# ble-jig-v1_0.net
KiCad netlist of a schematic drawn in EAGLE
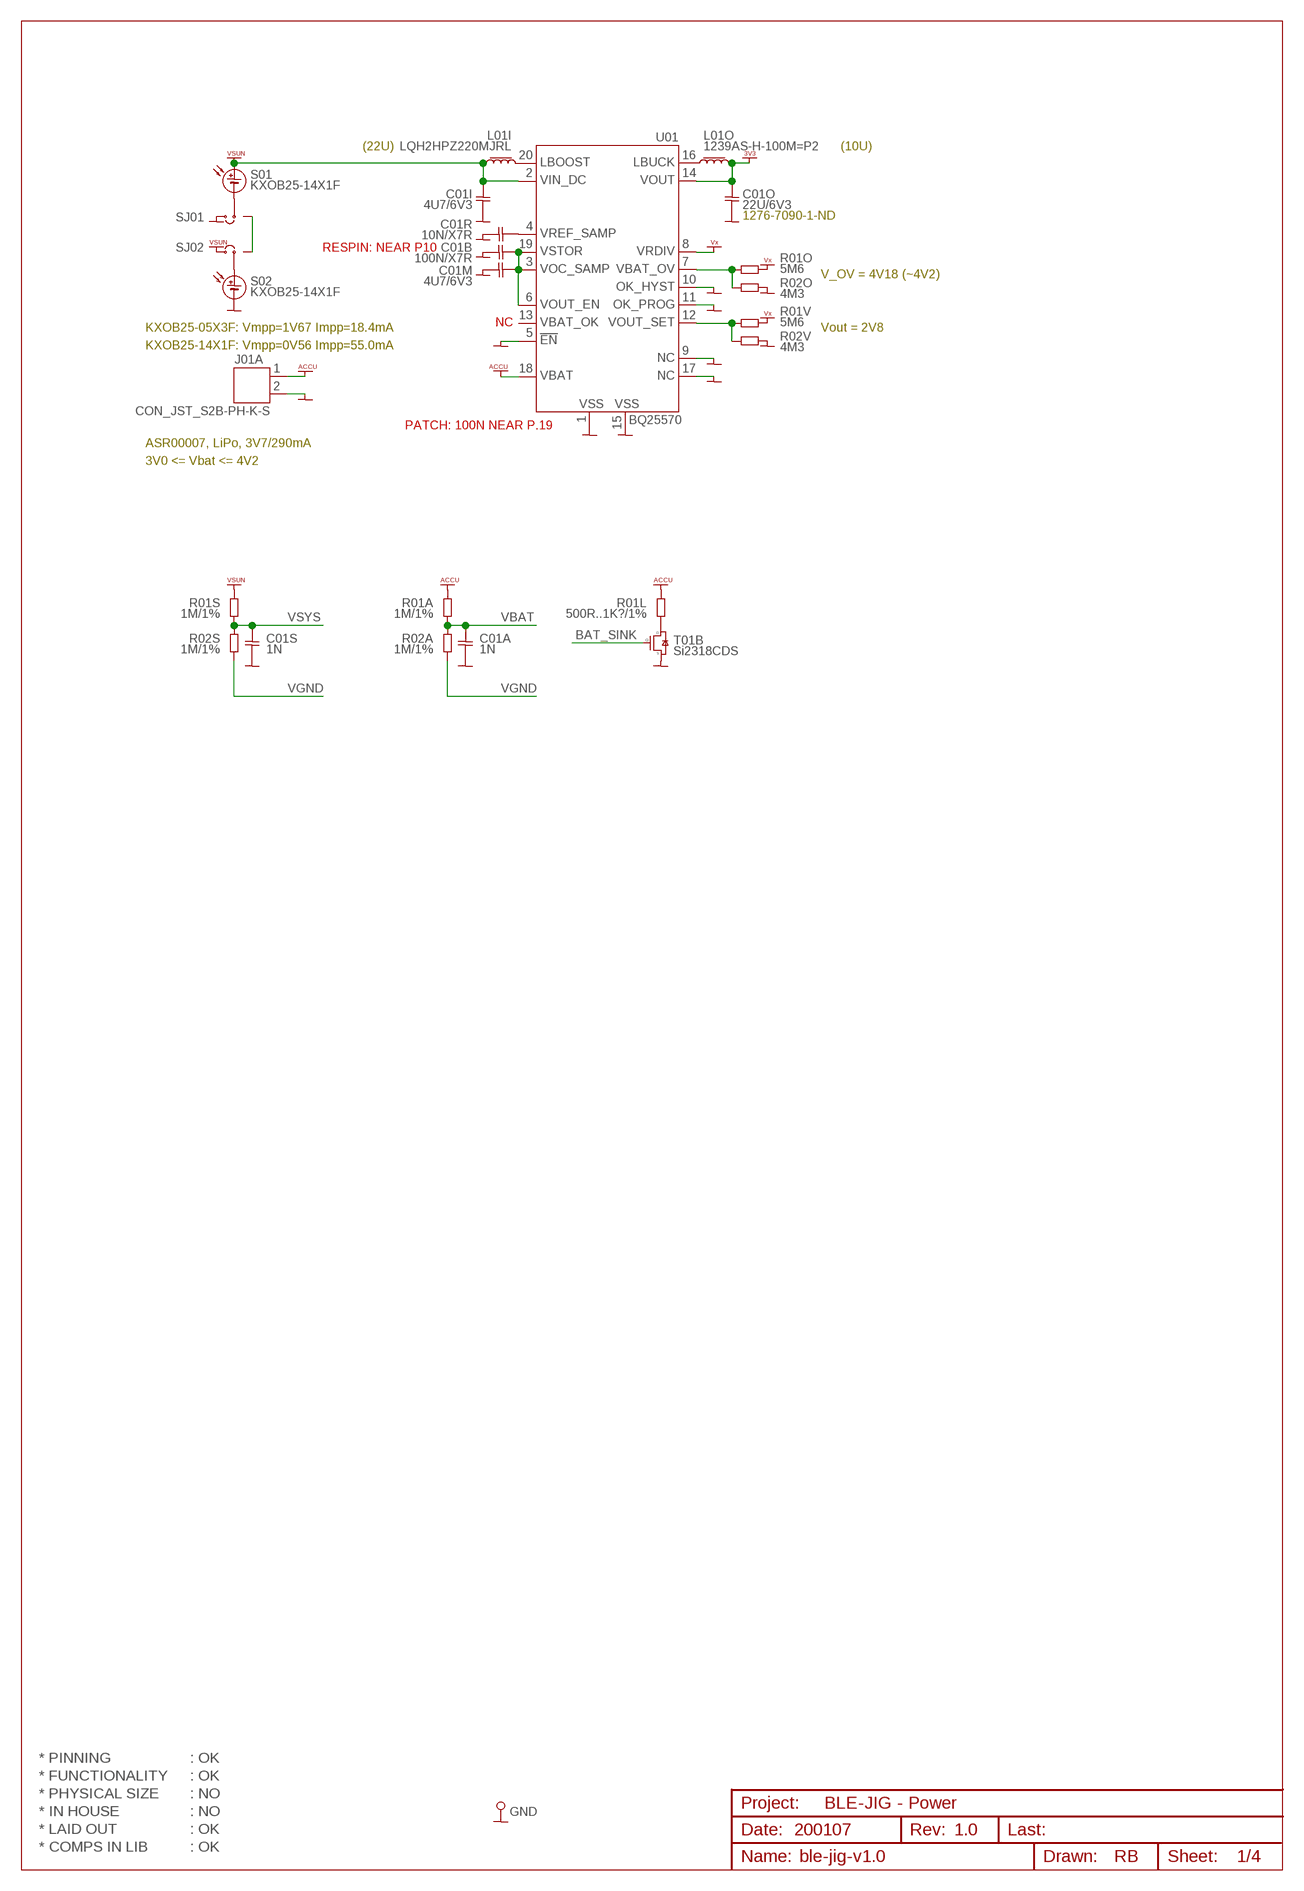
[diagram p0: schematic, sheet 1]
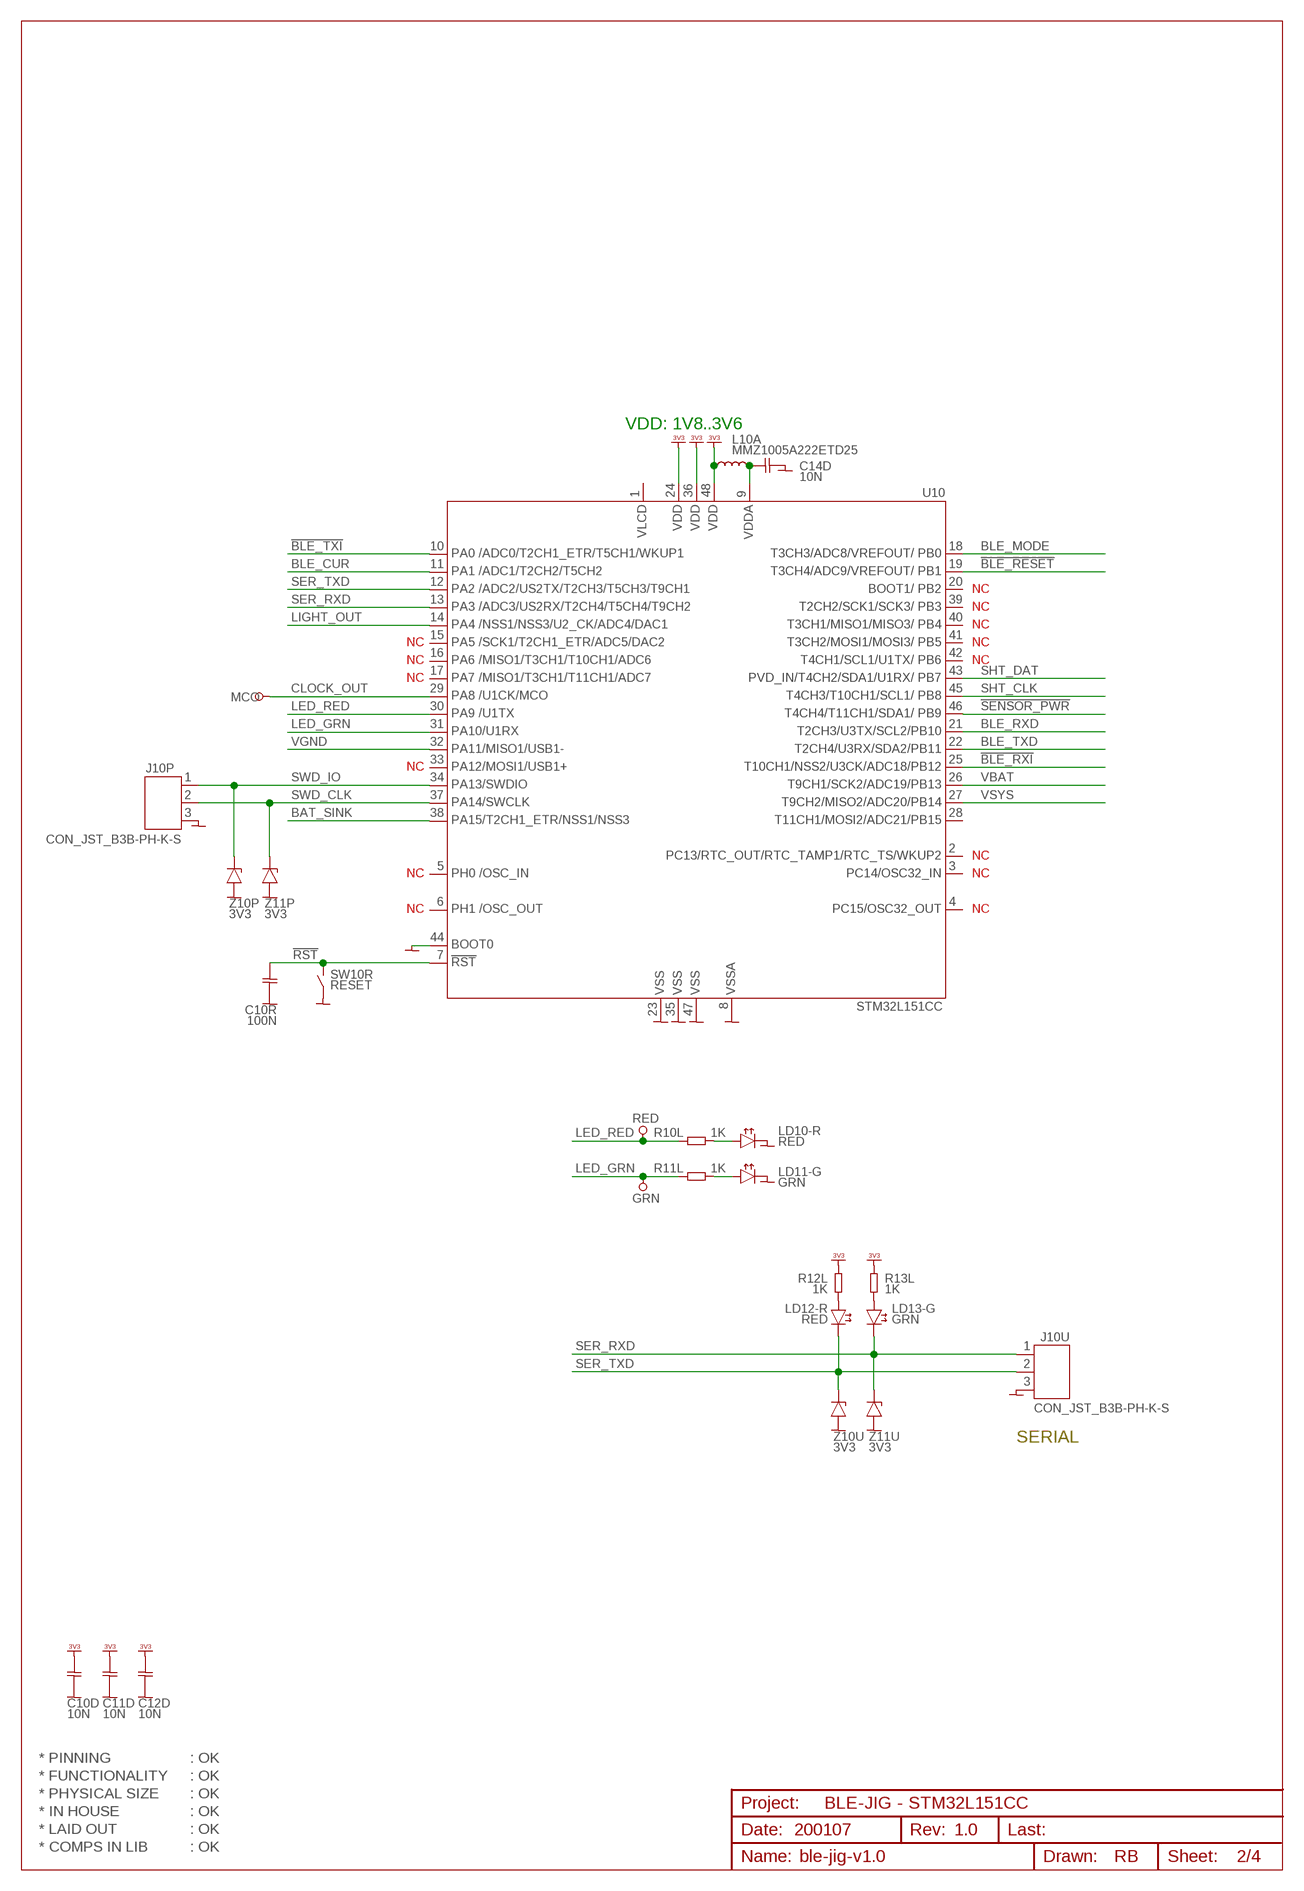
[diagram p1: schematic, sheet 2]
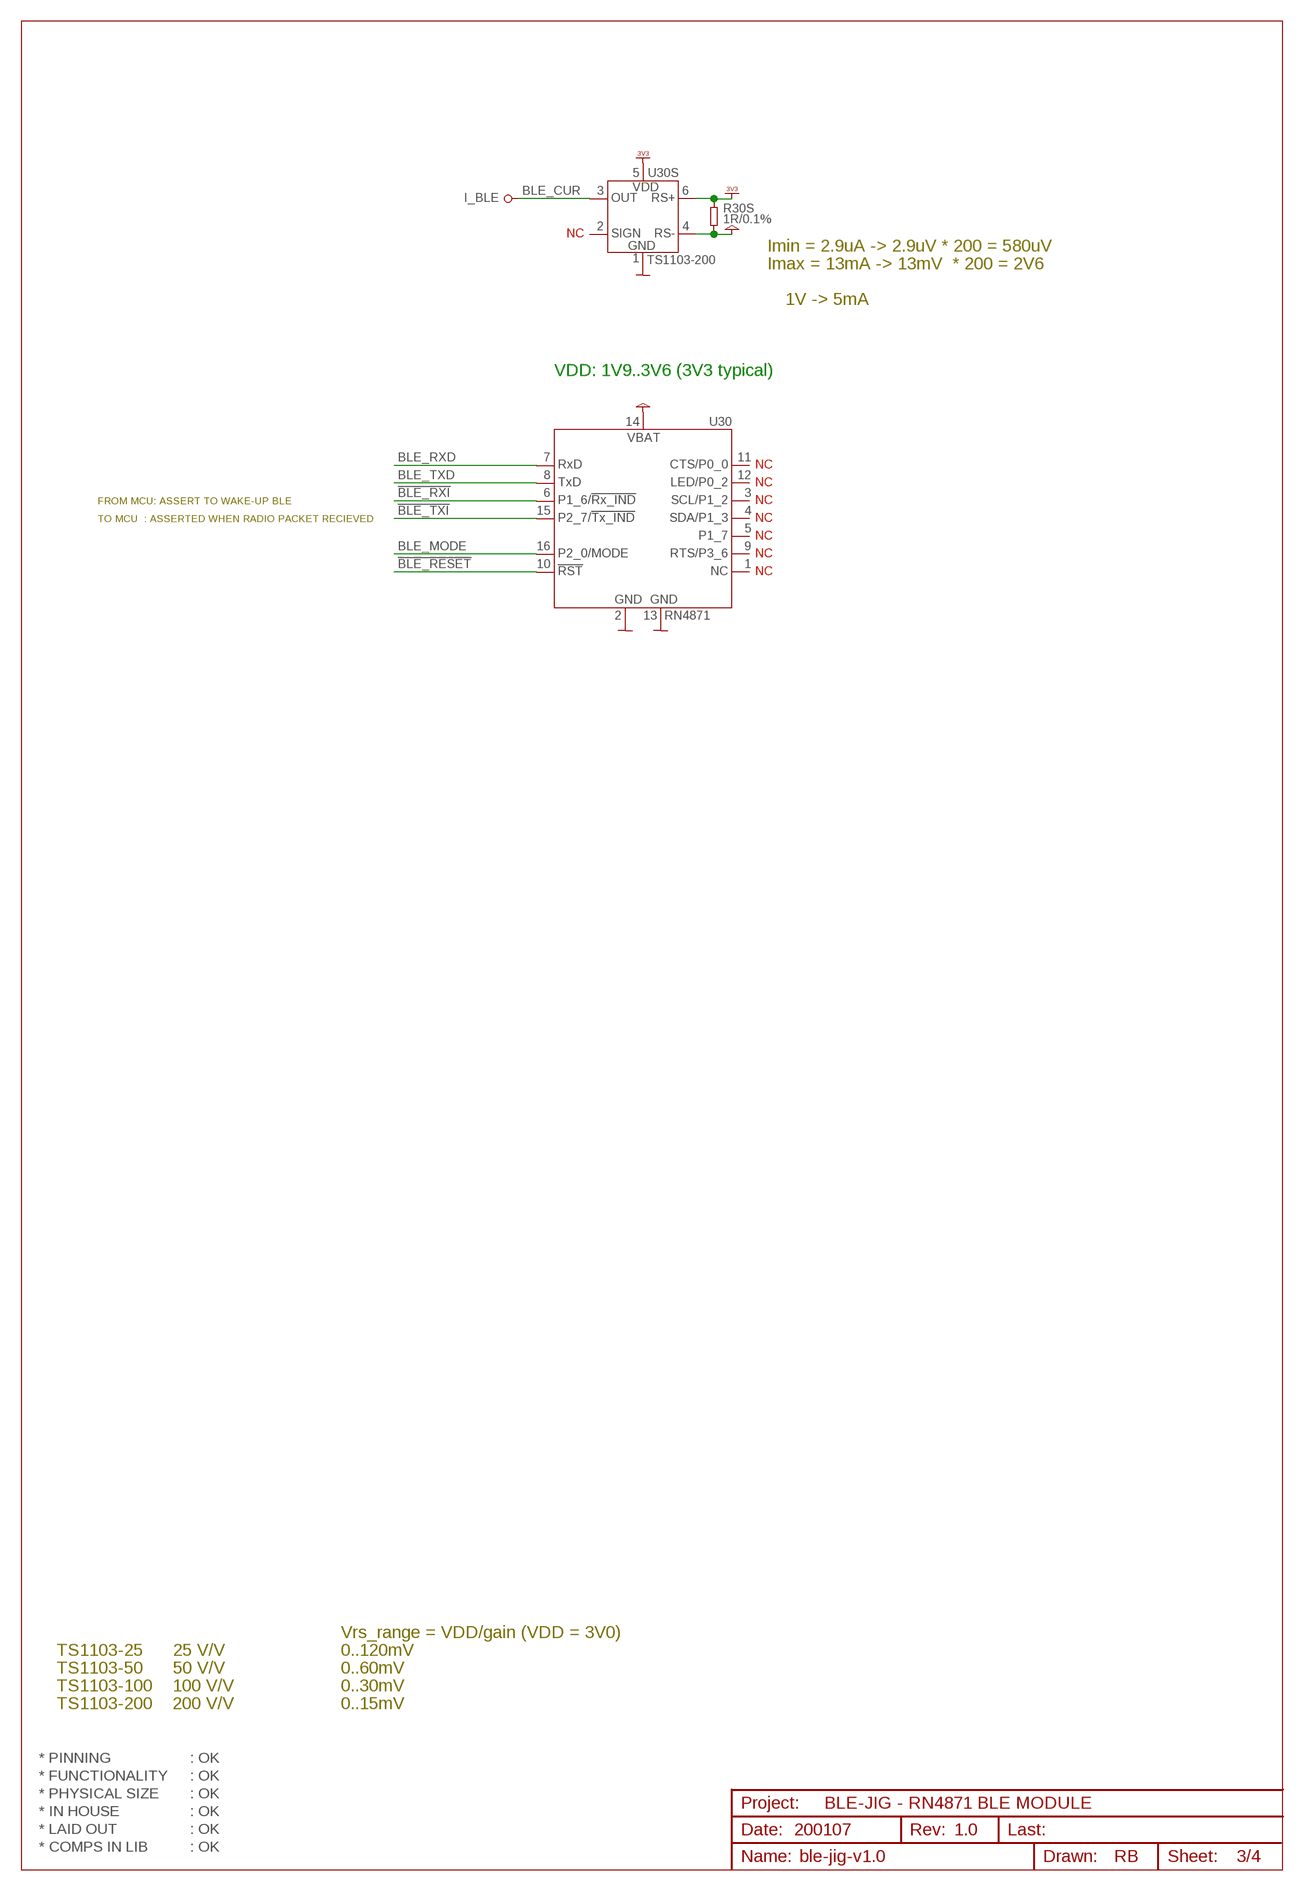
[diagram p2: schematic, sheet 3]
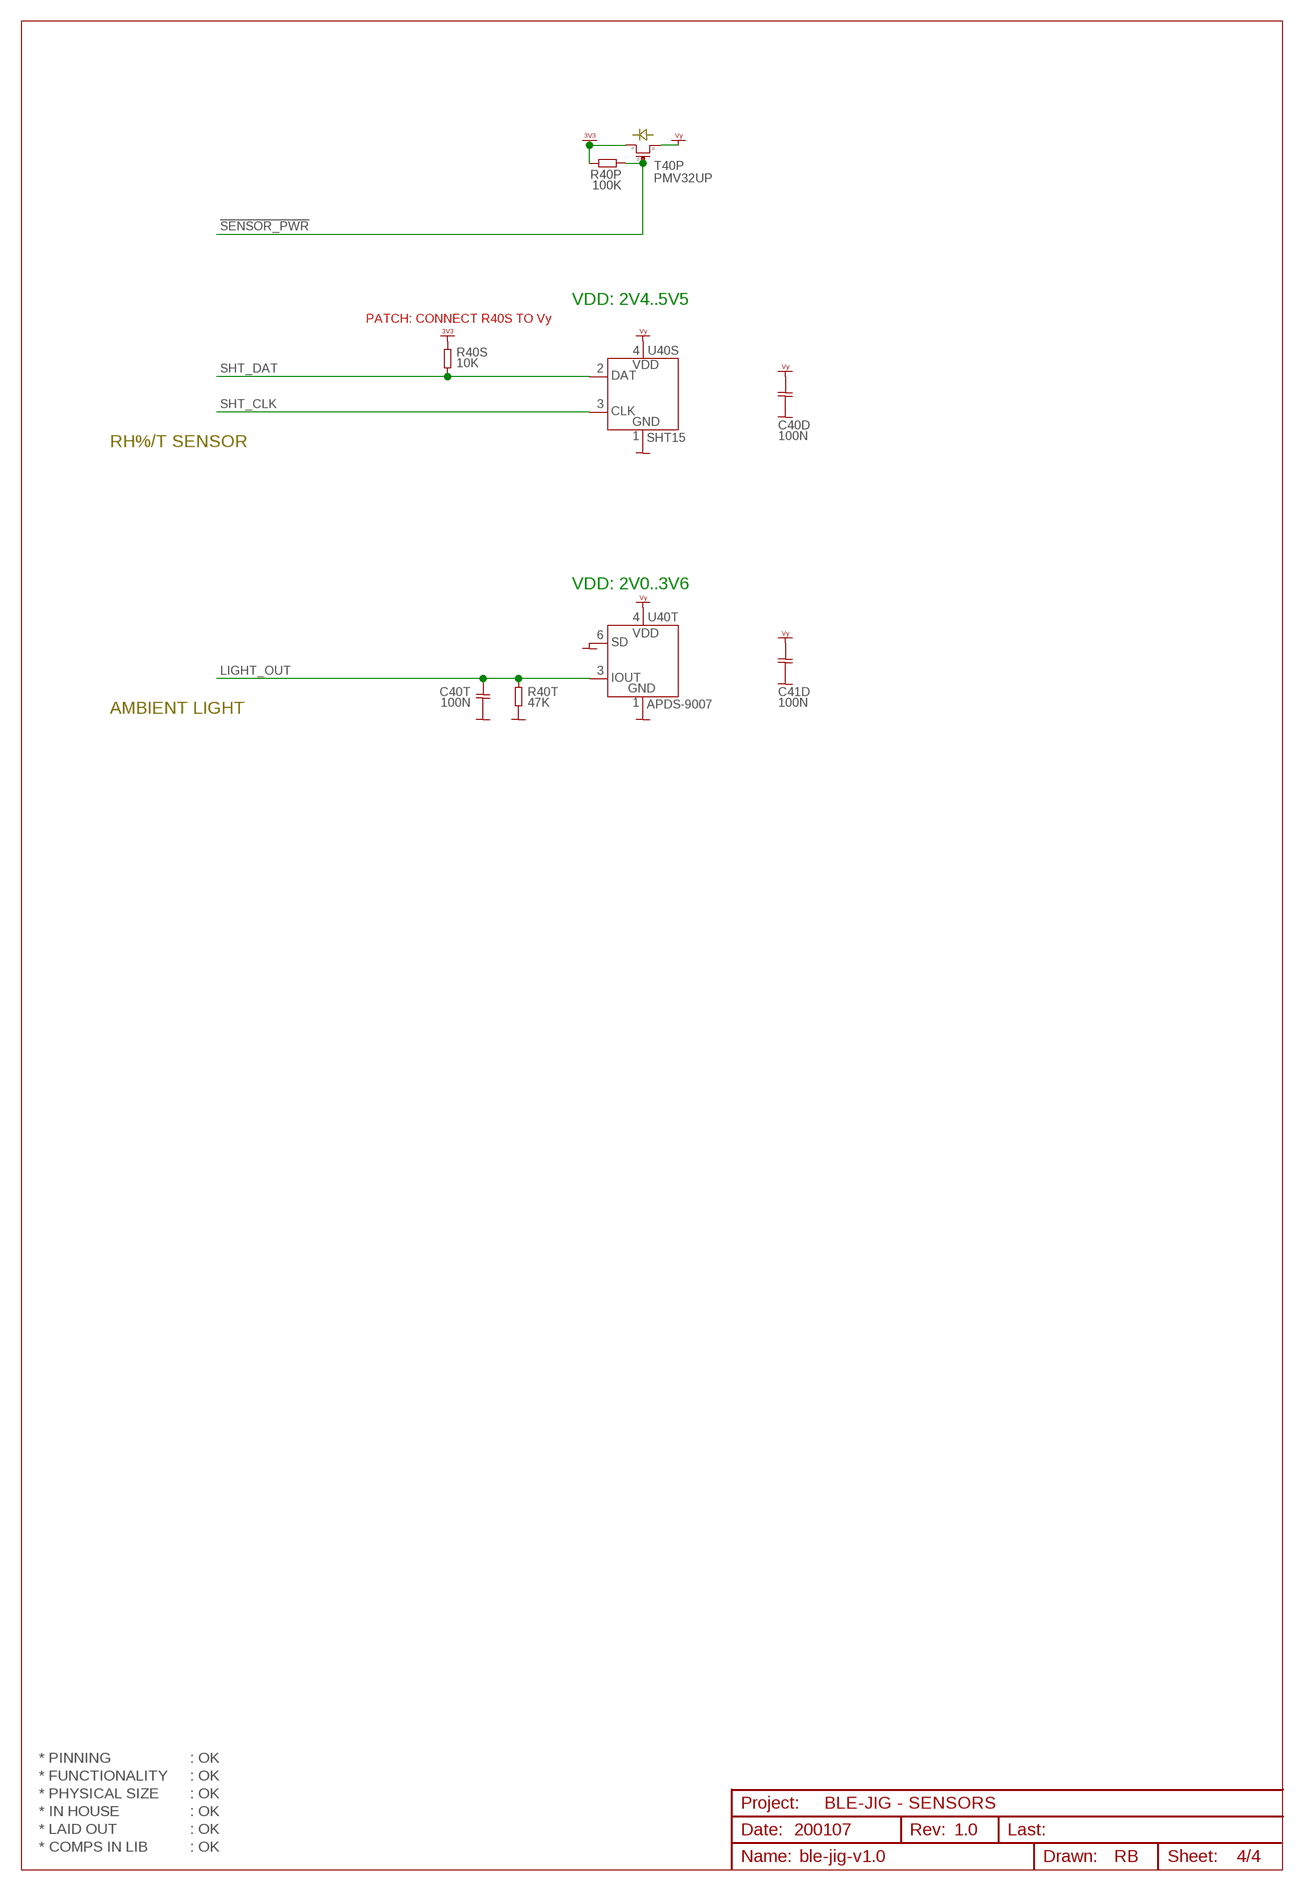
[diagram p3: schematic, sheet 4]

(export (version "E")
  (design (tool "Eeschema 10.0.6"))
  (components
    (comp (ref "C40D")
      (value "100N")
      (footprint "eagle-import:CAP0402")
      (libsource (lib "eagle-import") (part "CAP0402"))
    )
    (comp (ref "C40T")
      (value "100N")
      (footprint "eagle-import:CAP0402")
      (libsource (lib "eagle-import") (part "CAP0402"))
    )
    (comp (ref "C41D")
      (value "100N")
      (footprint "eagle-import:CAP0402")
      (libsource (lib "eagle-import") (part "CAP0402"))
    )
    (comp (ref "R40P")
      (value "100K")
      (footprint "eagle-import:RES0402")
      (libsource (lib "eagle-import") (part "RES0402"))
    )
    (comp (ref "R40S")
      (value "10K")
      (footprint "eagle-import:RES0402")
      (libsource (lib "eagle-import") (part "RES0402"))
    )
    (comp (ref "R40T")
      (value "47K")
      (footprint "eagle-import:RES0402")
      (libsource (lib "eagle-import") (part "RES0402"))
    )
    (comp (ref "T40P")
      (value "PMV32UP")
      (footprint "eagle-import:PFET_SOT23")
      (libsource (lib "eagle-import") (part "PFET_SOT23"))
    )
    (comp (ref "U40S")
      (value "SHT15")
      (footprint "eagle-import:SHT15")
      (libsource (lib "eagle-import") (part "SHT15"))
    )
    (comp (ref "U40T")
      (value "APDS-9007")
      (footprint "eagle-import:APDS-9007")
      (libsource (lib "eagle-import") (part "APDS-9007"))
    )
    (comp (ref "I_BLE")
      (value "PIN_TEST")
      (footprint "eagle-import:HOLE_PTH_0.8MM")
      (libsource (lib "eagle-import") (part "PIN_TEST"))
    )
    (comp (ref "R30S")
      (value "1R/0.1%")
      (footprint "eagle-import:RES0603")
      (libsource (lib "eagle-import") (part "RES0603"))
    )
    (comp (ref "U30")
      (value "RN4871")
      (footprint "eagle-import:RN4871")
      (libsource (lib "eagle-import") (part "RN4871"))
    )
    (comp (ref "U30S")
      (value "TS1103-200")
      (footprint "eagle-import:SOT23-6")
      (libsource (lib "eagle-import") (part "TS1103-200"))
    )
    (comp (ref "C10D")
      (value "10N")
      (footprint "eagle-import:CAP0402")
      (libsource (lib "eagle-import") (part "CAP0402"))
    )
    (comp (ref "C10R")
      (value "100N")
      (footprint "eagle-import:CAP0402")
      (libsource (lib "eagle-import") (part "CAP0402"))
    )
    (comp (ref "C11D")
      (value "10N")
      (footprint "eagle-import:CAP0402")
      (libsource (lib "eagle-import") (part "CAP0402"))
    )
    (comp (ref "C12D")
      (value "10N")
      (footprint "eagle-import:CAP0402")
      (libsource (lib "eagle-import") (part "CAP0402"))
    )
    (comp (ref "C14D")
      (value "10N")
      (footprint "eagle-import:CAP0402")
      (libsource (lib "eagle-import") (part "CAP0402"))
    )
    (comp (ref "GRN")
      (value "PIN_TEST_0.6MM")
      (footprint "eagle-import:HOLE_PTH_0.6MM")
      (libsource (lib "eagle-import") (part "PIN_TEST_0.6MM"))
    )
    (comp (ref "J10P")
      (value "CON_JST_B3B-PH-K-S")
      (footprint "eagle-import:CON_JST_B3B-PH-K-S")
      (libsource (lib "eagle-import") (part "CON_JST_B3B-PH-K-S"))
    )
    (comp (ref "J10U")
      (value "CON_JST_B3B-PH-K-S")
      (footprint "eagle-import:CON_JST_B3B-PH-K-S")
      (libsource (lib "eagle-import") (part "CON_JST_B3B-PH-K-S"))
    )
    (comp (ref "L10A")
      (value "MMZ1005A222ETD25")
      (footprint "eagle-import:L_0402")
      (libsource (lib "eagle-import") (part "L_0402"))
    )
    (comp (ref "LD10-R")
      (value "RED")
      (footprint "eagle-import:LED_SMD_0603")
      (libsource (lib "eagle-import") (part "LED_SMD_0603"))
    )
    (comp (ref "LD11-G")
      (value "GRN")
      (footprint "eagle-import:LED_SMD_0603")
      (libsource (lib "eagle-import") (part "LED_SMD_0603"))
    )
    (comp (ref "LD12-R")
      (value "RED")
      (footprint "eagle-import:LED_SMD_0603")
      (libsource (lib "eagle-import") (part "LED_SMD_0603"))
    )
    (comp (ref "LD13-G")
      (value "GRN")
      (footprint "eagle-import:LED_SMD_0603")
      (libsource (lib "eagle-import") (part "LED_SMD_0603"))
    )
    (comp (ref "MCO")
      (value "PIN_TEST")
      (footprint "eagle-import:HOLE_PTH_0.8MM")
      (libsource (lib "eagle-import") (part "PIN_TEST"))
    )
    (comp (ref "R10L")
      (value "1K")
      (footprint "eagle-import:RES0402")
      (libsource (lib "eagle-import") (part "RES0402"))
    )
    (comp (ref "R11L")
      (value "1K")
      (footprint "eagle-import:RES0402")
      (libsource (lib "eagle-import") (part "RES0402"))
    )
    (comp (ref "R12L")
      (value "1K")
      (footprint "eagle-import:RES0402")
      (libsource (lib "eagle-import") (part "RES0402"))
    )
    (comp (ref "R13L")
      (value "1K")
      (footprint "eagle-import:RES0402")
      (libsource (lib "eagle-import") (part "RES0402"))
    )
    (comp (ref "RED")
      (value "PIN_TEST_0.6MM")
      (footprint "eagle-import:HOLE_PTH_0.6MM")
      (libsource (lib "eagle-import") (part "PIN_TEST_0.6MM"))
    )
    (comp (ref "SW10R")
      (value "RESET")
      (footprint "eagle-import:SWITCH_PUSHBUTTON_EVP-AVAA1A")
      (libsource (lib "eagle-import") (part "SWITCH_PUSHBUTTON_EVP-AVAA1A"))
    )
    (comp (ref "U10")
      (value "STM32L151CC")
      (footprint "eagle-import:LQFP48")
      (libsource (lib "eagle-import") (part "STM32L151CC"))
    )
    (comp (ref "Z10P")
      (value "3V3")
      (footprint "eagle-import:ZENER_SOD80")
      (libsource (lib "eagle-import") (part "ZENER_SOD80"))
    )
    (comp (ref "Z10U")
      (value "3V3")
      (footprint "eagle-import:ZENER_SOD80")
      (libsource (lib "eagle-import") (part "ZENER_SOD80"))
    )
    (comp (ref "Z11P")
      (value "3V3")
      (footprint "eagle-import:ZENER_SOD80")
      (libsource (lib "eagle-import") (part "ZENER_SOD80"))
    )
    (comp (ref "Z11U")
      (value "3V3")
      (footprint "eagle-import:ZENER_SOD80")
      (libsource (lib "eagle-import") (part "ZENER_SOD80"))
    )
    (comp (ref "C01A")
      (value "1N")
      (footprint "eagle-import:CAP0402")
      (libsource (lib "eagle-import") (part "CAP0402"))
    )
    (comp (ref "C01B")
      (value "100N/X7R")
      (footprint "eagle-import:CAP0402")
      (libsource (lib "eagle-import") (part "CAP0402"))
    )
    (comp (ref "C01I")
      (value "4U7/6V3")
      (footprint "eagle-import:CAP0402")
      (libsource (lib "eagle-import") (part "CAP0402"))
    )
    (comp (ref "C01M")
      (value "4U7/6V3")
      (footprint "eagle-import:CAP0402")
      (libsource (lib "eagle-import") (part "CAP0402"))
    )
    (comp (ref "C01O")
      (value "22U/6V3")
      (footprint "eagle-import:CAP0402")
      (libsource (lib "eagle-import") (part "CAP0402"))
    )
    (comp (ref "C01R")
      (value "10N/X7R")
      (footprint "eagle-import:CAP0402")
      (libsource (lib "eagle-import") (part "CAP0402"))
    )
    (comp (ref "C01S")
      (value "1N")
      (footprint "eagle-import:CAP0402")
      (libsource (lib "eagle-import") (part "CAP0402"))
    )
    (comp (ref "GND")
      (value "PIN_TEST")
      (footprint "eagle-import:HOLE_PTH_0.8MM")
      (libsource (lib "eagle-import") (part "PIN_TEST"))
    )
    (comp (ref "J01A")
      (value "CON_JST_S2B-PH-K-S")
      (footprint "eagle-import:CON_JST_S2B-PH-K-S")
      (libsource (lib "eagle-import") (part "CON_JST_S2B-PH-K-S"))
    )
    (comp (ref "L01I")
      (value "LQH2HPZ220MJRL")
      (footprint "eagle-import:L_1008")
      (libsource (lib "eagle-import") (part "L_1008"))
    )
    (comp (ref "L01O")
      (value "1239AS-H-100M=P2")
      (footprint "eagle-import:L_1008")
      (libsource (lib "eagle-import") (part "L_1008"))
    )
    (comp (ref "R01A")
      (value "1M/1%")
      (footprint "eagle-import:RES0402")
      (libsource (lib "eagle-import") (part "RES0402"))
    )
    (comp (ref "R01L")
      (value "500R..1K?/1%")
      (footprint "eagle-import:RES0603")
      (libsource (lib "eagle-import") (part "RES0603"))
    )
    (comp (ref "R01O")
      (value "5M6")
      (footprint "eagle-import:RES0402")
      (libsource (lib "eagle-import") (part "RES0402"))
    )
    (comp (ref "R01S")
      (value "1M/1%")
      (footprint "eagle-import:RES0402")
      (libsource (lib "eagle-import") (part "RES0402"))
    )
    (comp (ref "R01V")
      (value "5M6")
      (footprint "eagle-import:RES0402")
      (libsource (lib "eagle-import") (part "RES0402"))
    )
    (comp (ref "R02A")
      (value "1M/1%")
      (footprint "eagle-import:RES0402")
      (libsource (lib "eagle-import") (part "RES0402"))
    )
    (comp (ref "R02O")
      (value "4M3")
      (footprint "eagle-import:RES0402")
      (libsource (lib "eagle-import") (part "RES0402"))
    )
    (comp (ref "R02S")
      (value "1M/1%")
      (footprint "eagle-import:RES0402")
      (libsource (lib "eagle-import") (part "RES0402"))
    )
    (comp (ref "R02V")
      (value "4M3")
      (footprint "eagle-import:RES0402")
      (libsource (lib "eagle-import") (part "RES0402"))
    )
    (comp (ref "S01")
      (value "KXOB25-14X1F")
      (footprint "eagle-import:KXOB25-14X1F")
      (libsource (lib "eagle-import") (part "KXOB25-14X1F"))
    )
    (comp (ref "S02")
      (value "KXOB25-14X1F")
      (footprint "eagle-import:KXOB25-14X1F")
      (libsource (lib "eagle-import") (part "KXOB25-14X1F"))
    )
    (comp (ref "SJ01")
      (value "SJ3SJ3-S")
      (footprint "eagle-import:SJ3-S")
      (libsource (lib "eagle-import") (part "SJ3SJ3-S"))
    )
    (comp (ref "SJ02")
      (value "SJ3SJ3-S")
      (footprint "eagle-import:SJ3-S")
      (libsource (lib "eagle-import") (part "SJ3SJ3-S"))
    )
    (comp (ref "T01B")
      (value "Si2318CDS")
      (footprint "eagle-import:NFET_SOT23")
      (libsource (lib "eagle-import") (part "NFET_SOT23"))
    )
    (comp (ref "U01")
      (value "BQ25570")
      (footprint "eagle-import:VQFN20")
      (libsource (lib "eagle-import") (part "BQ25570"))
    )
  )
  (nets
    (net (code "1") (name "ACCU") (class "Default")
      (node (ref "J01A") (pin "1") (pinfunction "1_1") (pintype "passive"))
      (node (ref "R01A") (pin "2") (pinfunction "2_2") (pintype "passive"))
      (node (ref "R01L") (pin "2") (pinfunction "2_2") (pintype "passive"))
      (node (ref "U01") (pin "18") (pinfunction "18.VBAT_18") (pintype "passive"))
    )
    (net (code "2") (name "BAT_SINK") (class "Default")
      (node (ref "T01B") (pin "1") (pinfunction "G1_1") (pintype "bidirectional"))
      (node (ref "U10") (pin "38") (pinfunction "38.PA15_38") (pintype "passive"))
    )
    (net (code "3") (name "BLE_CUR") (class "Default")
      (node (ref "I_BLE") (pin "1") (pinfunction "P$1_1") (pintype "passive"))
      (node (ref "U10") (pin "11") (pinfunction "11.PA1_11") (pintype "passive"))
      (node (ref "U30S") (pin "3") (pinfunction "3.OUT_3") (pintype "passive"))
    )
    (net (code "4") (name "BLE_MODE") (class "Default")
      (node (ref "U10") (pin "18") (pinfunction "18.PB0_18") (pintype "passive"))
      (node (ref "U30") (pin "16") (pinfunction "16.P2_0_16") (pintype "passive"))
    )
    (net (code "5") (name "BLE_RXD") (class "Default")
      (node (ref "U10") (pin "21") (pinfunction "21.PB10_21") (pintype "passive"))
      (node (ref "U30") (pin "7") (pinfunction "7.RXD_7") (pintype "passive"))
    )
    (net (code "6") (name "BLE_TXD") (class "Default")
      (node (ref "U10") (pin "22") (pinfunction "22.PB11_22") (pintype "passive"))
      (node (ref "U30") (pin "8") (pinfunction "8.TXD_8") (pintype "passive"))
    )
    (net (code "7") (name "CLOCK_OUT") (class "Default")
      (node (ref "MCO") (pin "1") (pinfunction "P$1_1") (pintype "passive"))
      (node (ref "U10") (pin "29") (pinfunction "29.PA8_29") (pintype "passive"))
    )
    (net (code "8") (name "GND") (class "Default")
      (node (ref "C01A") (pin "2") (pinfunction "2_2") (pintype "passive"))
      (node (ref "C01B") (pin "2") (pinfunction "2_2") (pintype "passive"))
      (node (ref "C01I") (pin "2") (pinfunction "2_2") (pintype "passive"))
      (node (ref "C01M") (pin "2") (pinfunction "2_2") (pintype "passive"))
      (node (ref "C01O") (pin "2") (pinfunction "2_2") (pintype "passive"))
      (node (ref "C01R") (pin "2") (pinfunction "2_2") (pintype "passive"))
      (node (ref "C01S") (pin "2") (pinfunction "2_2") (pintype "passive"))
      (node (ref "C10D") (pin "2") (pinfunction "2_2") (pintype "passive"))
      (node (ref "C10R") (pin "2") (pinfunction "2_2") (pintype "passive"))
      (node (ref "C11D") (pin "2") (pinfunction "2_2") (pintype "passive"))
      (node (ref "C12D") (pin "2") (pinfunction "2_2") (pintype "passive"))
      (node (ref "C14D") (pin "2") (pinfunction "2_2") (pintype "passive"))
      (node (ref "C40D") (pin "2") (pinfunction "2_2") (pintype "passive"))
      (node (ref "C40T") (pin "2") (pinfunction "2_2") (pintype "passive"))
      (node (ref "C41D") (pin "2") (pinfunction "2_2") (pintype "passive"))
      (node (ref "GND") (pin "1") (pinfunction "P$1_1") (pintype "passive"))
      (node (ref "J01A") (pin "2") (pinfunction "2_2") (pintype "passive"))
      (node (ref "J10P") (pin "3") (pinfunction "3_3") (pintype "passive"))
      (node (ref "J10U") (pin "3") (pinfunction "3_3") (pintype "passive"))
      (node (ref "LD10-R") (pin "C") (pinfunction "C_C") (pintype "passive"))
      (node (ref "LD11-G") (pin "C") (pinfunction "C_C") (pintype "passive"))
      (node (ref "R02O") (pin "2") (pinfunction "2_2") (pintype "passive"))
      (node (ref "R02V") (pin "2") (pinfunction "2_2") (pintype "passive"))
      (node (ref "R40T") (pin "2") (pinfunction "2_2") (pintype "passive"))
      (node (ref "S02") (pin "2") (pinfunction "2_2") (pintype "passive"))
      (node (ref "SJ01") (pin "1") (pinfunction "1_1") (pintype "passive"))
      (node (ref "SW10R") (pin "2") (pinfunction "3-4_2") (pintype "passive"))
      (node (ref "T01B") (pin "2") (pinfunction "S2_2") (pintype "bidirectional"))
      (node (ref "U01") (pin "1") (pinfunction "1.VSS_1") (pintype "passive"))
      (node (ref "U01") (pin "10") (pinfunction "10.OK_HYST_10") (pintype "passive"))
      (node (ref "U01") (pin "11") (pinfunction "11.OK_PROG_11") (pintype "passive"))
      (node (ref "U01") (pin "15") (pinfunction "15.VSS_15") (pintype "passive"))
      (node (ref "U01") (pin "17") (pinfunction "17.NC_17") (pintype "passive"))
      (node (ref "U01") (pin "5") (pinfunction "5.~{EN}_5") (pintype "passive"))
      (node (ref "U01") (pin "9") (pinfunction "9.NC_9") (pintype "passive"))
      (node (ref "U01") (pin "TP") (pinfunction "15.VSS_TP") (pintype "passive"))
      (node (ref "U01") (pin "V1") (pinfunction "15.VSS_V1") (pintype "passive"))
      (node (ref "U01") (pin "V2") (pinfunction "15.VSS_V2") (pintype "passive"))
      (node (ref "U01") (pin "V3") (pinfunction "15.VSS_V3") (pintype "passive"))
      (node (ref "U01") (pin "V4") (pinfunction "15.VSS_V4") (pintype "passive"))
      (node (ref "U10") (pin "23") (pinfunction "23.GND_23") (pintype "passive"))
      (node (ref "U10") (pin "35") (pinfunction "35.GND_35") (pintype "passive"))
      (node (ref "U10") (pin "44") (pinfunction "44.BOOT0_44") (pintype "passive"))
      (node (ref "U10") (pin "47") (pinfunction "47.GND_47") (pintype "passive"))
      (node (ref "U10") (pin "8") (pinfunction "8.GND_8") (pintype "passive"))
      (node (ref "U30") (pin "13") (pinfunction "13.GND_13") (pintype "passive"))
      (node (ref "U30") (pin "2") (pinfunction "2.GND_2") (pintype "passive"))
      (node (ref "U30S") (pin "1") (pinfunction "1.GND_1") (pintype "passive"))
      (node (ref "U40S") (pin "1") (pinfunction "1.GND_1") (pintype "passive"))
      (node (ref "U40T") (pin "1") (pinfunction "1.GND_1") (pintype "passive"))
      (node (ref "U40T") (pin "6") (pinfunction "6.SD_6") (pintype "passive"))
      (node (ref "Z10P") (pin "1") (pinfunction "+_1") (pintype "passive"))
      (node (ref "Z10U") (pin "1") (pinfunction "+_1") (pintype "passive"))
      (node (ref "Z11P") (pin "1") (pinfunction "+_1") (pintype "passive"))
      (node (ref "Z11U") (pin "1") (pinfunction "+_1") (pintype "passive"))
    )
    (net (code "9") (name "LED_GRN") (class "Default")
      (node (ref "GRN") (pin "1") (pinfunction "P$1_1") (pintype "passive"))
      (node (ref "R11L") (pin "1") (pinfunction "1_1") (pintype "passive"))
      (node (ref "U10") (pin "31") (pinfunction "31.PA10_31") (pintype "passive"))
    )
    (net (code "10") (name "LED_RED") (class "Default")
      (node (ref "R10L") (pin "1") (pinfunction "1_1") (pintype "passive"))
      (node (ref "RED") (pin "1") (pinfunction "P$1_1") (pintype "passive"))
      (node (ref "U10") (pin "30") (pinfunction "30.PA9_30") (pintype "passive"))
    )
    (net (code "11") (name "LIGHT_OUT") (class "Default")
      (node (ref "C40T") (pin "1") (pinfunction "1_1") (pintype "passive"))
      (node (ref "R40T") (pin "1") (pinfunction "1_1") (pintype "passive"))
      (node (ref "U10") (pin "14") (pinfunction "14.PA4_14") (pintype "passive"))
      (node (ref "U40T") (pin "3") (pinfunction "3.IOUT_3") (pintype "passive"))
    )
    (net (code "12") (name "Net-(LD10-R-PadA)") (class "Default")
      (node (ref "LD10-R") (pin "A") (pinfunction "A_A") (pintype "passive"))
      (node (ref "R10L") (pin "2") (pinfunction "2_2") (pintype "passive"))
    )
    (net (code "13") (name "Net-(LD11-G-PadA)") (class "Default")
      (node (ref "LD11-G") (pin "A") (pinfunction "A_A") (pintype "passive"))
      (node (ref "R11L") (pin "2") (pinfunction "2_2") (pintype "passive"))
    )
    (net (code "14") (name "Net-(LD12-R-PadA)") (class "Default")
      (node (ref "LD12-R") (pin "A") (pinfunction "A_A") (pintype "passive"))
      (node (ref "R12L") (pin "2") (pinfunction "2_2") (pintype "passive"))
    )
    (net (code "15") (name "Net-(LD13-G-PadA)") (class "Default")
      (node (ref "LD13-G") (pin "A") (pinfunction "A_A") (pintype "passive"))
      (node (ref "R13L") (pin "2") (pinfunction "2_2") (pintype "passive"))
    )
    (net (code "16") (name "Net-(S01-Pad2)") (class "Default")
      (node (ref "S01") (pin "2") (pinfunction "2_2") (pintype "passive"))
      (node (ref "SJ01") (pin "2") (pinfunction "2_2") (pintype "passive"))
    )
    (net (code "17") (name "Net-(S02-Pad1)") (class "Default")
      (node (ref "S02") (pin "1") (pinfunction "1_1") (pintype "passive"))
      (node (ref "SJ02") (pin "2") (pinfunction "2_2") (pintype "passive"))
    )
    (net (code "18") (name "Net-(SJ01-Pad3)") (class "Default")
      (node (ref "SJ01") (pin "3") (pinfunction "3_3") (pintype "passive"))
      (node (ref "SJ02") (pin "3") (pinfunction "3_3") (pintype "passive"))
    )
    (net (code "19") (name "Net-(T01B-D3)") (class "Default")
      (node (ref "R01L") (pin "1") (pinfunction "1_1") (pintype "passive"))
      (node (ref "T01B") (pin "3") (pinfunction "D3_3") (pintype "bidirectional"))
    )
    (net (code "20") (name "Net-(U01-4.VREF_SAMP)") (class "Default")
      (node (ref "C01R") (pin "1") (pinfunction "1_1") (pintype "passive"))
      (node (ref "U01") (pin "4") (pinfunction "4.VREF_SAMP_4") (pintype "passive"))
    )
    (net (code "21") (name "Net-(U01-7.VBAT_OV)") (class "Default")
      (node (ref "R01O") (pin "2") (pinfunction "2_2") (pintype "passive"))
      (node (ref "R02O") (pin "1") (pinfunction "1_1") (pintype "passive"))
      (node (ref "U01") (pin "7") (pinfunction "7.VBAT_OV_7") (pintype "passive"))
    )
    (net (code "22") (name "Net-(U01-12.VOUT_SET)") (class "Default")
      (node (ref "R01V") (pin "2") (pinfunction "2_2") (pintype "passive"))
      (node (ref "R02V") (pin "1") (pinfunction "1_1") (pintype "passive"))
      (node (ref "U01") (pin "12") (pinfunction "12.VOUT_SET_12") (pintype "passive"))
    )
    (net (code "23") (name "Net-(U01-16.LBUCK)") (class "Default")
      (node (ref "L01O") (pin "1") (pinfunction "1_1") (pintype "passive"))
      (node (ref "U01") (pin "16") (pinfunction "16.LBUCK_16") (pintype "passive"))
    )
    (net (code "24") (name "Net-(U01-19.VSTOR)") (class "Default")
      (node (ref "C01B") (pin "1") (pinfunction "1_1") (pintype "passive"))
      (node (ref "C01M") (pin "1") (pinfunction "1_1") (pintype "passive"))
      (node (ref "U01") (pin "19") (pinfunction "19.VSTOR_19") (pintype "passive"))
      (node (ref "U01") (pin "3") (pinfunction "3.VOC_SAMP_3") (pintype "passive"))
      (node (ref "U01") (pin "6") (pinfunction "6.VOUT_EN_6") (pintype "passive"))
    )
    (net (code "25") (name "Net-(U01-20.LBOOST)") (class "Default")
      (node (ref "L01I") (pin "2") (pinfunction "2_2") (pintype "passive"))
      (node (ref "U01") (pin "20") (pinfunction "20.LBOOST_20") (pintype "passive"))
    )
    (net (code "26") (name "Net-(U10-9.VDD)") (class "Default")
      (node (ref "C14D") (pin "1") (pinfunction "1_1") (pintype "passive"))
      (node (ref "L10A") (pin "2") (pinfunction "2_2") (pintype "passive"))
      (node (ref "U10") (pin "9") (pinfunction "9.VDD_9") (pintype "passive"))
    )
    (net (code "27") (name "SER_RXD") (class "Default")
      (node (ref "J10U") (pin "1") (pinfunction "1_1") (pintype "passive"))
      (node (ref "LD13-G") (pin "C") (pinfunction "C_C") (pintype "passive"))
      (node (ref "U10") (pin "13") (pinfunction "13.PA3_13") (pintype "passive"))
      (node (ref "Z11U") (pin "2") (pinfunction "-_2") (pintype "passive"))
    )
    (net (code "28") (name "SER_TXD") (class "Default")
      (node (ref "J10U") (pin "2") (pinfunction "2_2") (pintype "passive"))
      (node (ref "LD12-R") (pin "C") (pinfunction "C_C") (pintype "passive"))
      (node (ref "U10") (pin "12") (pinfunction "12.PA2_12") (pintype "passive"))
      (node (ref "Z10U") (pin "2") (pinfunction "-_2") (pintype "passive"))
    )
    (net (code "29") (name "SHT_CLK") (class "Default")
      (node (ref "U10") (pin "45") (pinfunction "45.PB8_45") (pintype "passive"))
      (node (ref "U40S") (pin "3") (pinfunction "3.CLK_3") (pintype "passive"))
    )
    (net (code "30") (name "SHT_DAT") (class "Default")
      (node (ref "R40S") (pin "2") (pinfunction "2_2") (pintype "passive"))
      (node (ref "U10") (pin "43") (pinfunction "43.PB7_43") (pintype "passive"))
      (node (ref "U40S") (pin "2") (pinfunction "2.DAT_2") (pintype "passive"))
    )
    (net (code "31") (name "SWD_CLK") (class "Default")
      (node (ref "J10P") (pin "2") (pinfunction "2_2") (pintype "passive"))
      (node (ref "U10") (pin "37") (pinfunction "37.PA14_37") (pintype "passive"))
      (node (ref "Z11P") (pin "2") (pinfunction "-_2") (pintype "passive"))
    )
    (net (code "32") (name "SWD_IO") (class "Default")
      (node (ref "J10P") (pin "1") (pinfunction "1_1") (pintype "passive"))
      (node (ref "U10") (pin "34") (pinfunction "34.PA13_34") (pintype "passive"))
      (node (ref "Z10P") (pin "2") (pinfunction "-_2") (pintype "passive"))
    )
    (net (code "33") (name "VBAT") (class "Default")
      (node (ref "C01A") (pin "1") (pinfunction "1_1") (pintype "passive"))
      (node (ref "R01A") (pin "1") (pinfunction "1_1") (pintype "passive"))
      (node (ref "R02A") (pin "2") (pinfunction "2_2") (pintype "passive"))
      (node (ref "U10") (pin "26") (pinfunction "26.PB13_26") (pintype "passive"))
    )
    (net (code "34") (name "VCC") (class "Default")
      (node (ref "R30S") (pin "2") (pinfunction "2_2") (pintype "passive"))
      (node (ref "U30") (pin "14") (pinfunction "14.VBAT_14") (pintype "passive"))
      (node (ref "U30S") (pin "4") (pinfunction "4.RS-_4") (pintype "passive"))
    )
    (net (code "35") (name "VDD_3V3") (class "Default")
      (node (ref "C01O") (pin "1") (pinfunction "1_1") (pintype "passive"))
      (node (ref "C10D") (pin "1") (pinfunction "1_1") (pintype "passive"))
      (node (ref "C11D") (pin "1") (pinfunction "1_1") (pintype "passive"))
      (node (ref "C12D") (pin "1") (pinfunction "1_1") (pintype "passive"))
      (node (ref "L01O") (pin "2") (pinfunction "2_2") (pintype "passive"))
      (node (ref "L10A") (pin "1") (pinfunction "1_1") (pintype "passive"))
      (node (ref "R12L") (pin "1") (pinfunction "1_1") (pintype "passive"))
      (node (ref "R13L") (pin "1") (pinfunction "1_1") (pintype "passive"))
      (node (ref "R30S") (pin "1") (pinfunction "1_1") (pintype "passive"))
      (node (ref "R40P") (pin "1") (pinfunction "1_1") (pintype "passive"))
      (node (ref "R40S") (pin "1") (pinfunction "1_1") (pintype "passive"))
      (node (ref "T40P") (pin "2") (pinfunction "S_2") (pintype "bidirectional"))
      (node (ref "U01") (pin "14") (pinfunction "14.VOUT_14") (pintype "passive"))
      (node (ref "U10") (pin "24") (pinfunction "24.VDD_24") (pintype "passive"))
      (node (ref "U10") (pin "36") (pinfunction "36.VDD_36") (pintype "passive"))
      (node (ref "U10") (pin "48") (pinfunction "48.VDD_48") (pintype "passive"))
      (node (ref "U30S") (pin "5") (pinfunction "5.VDD_5") (pintype "passive"))
      (node (ref "U30S") (pin "6") (pinfunction "6.RS+_6") (pintype "passive"))
    )
    (net (code "36") (name "VGND") (class "Default")
      (node (ref "R02A") (pin "1") (pinfunction "1_1") (pintype "passive"))
      (node (ref "R02S") (pin "1") (pinfunction "1_1") (pintype "passive"))
      (node (ref "U10") (pin "32") (pinfunction "32.PA11_32") (pintype "passive"))
    )
    (net (code "37") (name "VSUN") (class "Default")
      (node (ref "C01I") (pin "1") (pinfunction "1_1") (pintype "passive"))
      (node (ref "L01I") (pin "1") (pinfunction "1_1") (pintype "passive"))
      (node (ref "R01S") (pin "2") (pinfunction "2_2") (pintype "passive"))
      (node (ref "S01") (pin "1") (pinfunction "1_1") (pintype "passive"))
      (node (ref "SJ02") (pin "1") (pinfunction "1_1") (pintype "passive"))
      (node (ref "U01") (pin "2") (pinfunction "2.VIN_DC_2") (pintype "passive"))
    )
    (net (code "38") (name "VSYS") (class "Default")
      (node (ref "C01S") (pin "1") (pinfunction "1_1") (pintype "passive"))
      (node (ref "R01S") (pin "1") (pinfunction "1_1") (pintype "passive"))
      (node (ref "R02S") (pin "2") (pinfunction "2_2") (pintype "passive"))
      (node (ref "U10") (pin "27") (pinfunction "27.PB14_27") (pintype "passive"))
    )
    (net (code "39") (name "VX") (class "Default")
      (node (ref "R01O") (pin "1") (pinfunction "1_1") (pintype "passive"))
      (node (ref "R01V") (pin "1") (pinfunction "1_1") (pintype "passive"))
      (node (ref "U01") (pin "8") (pinfunction "8.VRDIV_8") (pintype "passive"))
    )
    (net (code "40") (name "VY") (class "Default")
      (node (ref "C40D") (pin "1") (pinfunction "1_1") (pintype "passive"))
      (node (ref "C41D") (pin "1") (pinfunction "1_1") (pintype "passive"))
      (node (ref "T40P") (pin "3") (pinfunction "D_3") (pintype "bidirectional"))
      (node (ref "U40S") (pin "4") (pinfunction "4.VDD_4") (pintype "passive"))
      (node (ref "U40T") (pin "4") (pinfunction "4.VDD_4") (pintype "passive"))
    )
    (net (code "41") (name "unconnected-(U01-13.VBAT_OK-Pad13)") (class "Default")
      (node (ref "U01") (pin "13") (pinfunction "13.VBAT_OK_13") (pintype "passive"))
    )
    (net (code "42") (name "unconnected-(U10-1.VDD-Pad1)") (class "Default")
      (node (ref "U10") (pin "1") (pinfunction "1.VDD_1") (pintype "passive"))
    )
    (net (code "43") (name "unconnected-(U10-2.PC13-Pad2)") (class "Default")
      (node (ref "U10") (pin "2") (pinfunction "2.PC13_2") (pintype "passive"))
    )
    (net (code "44") (name "unconnected-(U10-3.PC14-Pad3)") (class "Default")
      (node (ref "U10") (pin "3") (pinfunction "3.PC14_3") (pintype "passive"))
    )
    (net (code "45") (name "unconnected-(U10-4.PC15-Pad4)") (class "Default")
      (node (ref "U10") (pin "4") (pinfunction "4.PC15_4") (pintype "passive"))
    )
    (net (code "46") (name "unconnected-(U10-5.OSC_IN-Pad5)") (class "Default")
      (node (ref "U10") (pin "5") (pinfunction "5.OSC_IN_5") (pintype "passive"))
    )
    (net (code "47") (name "unconnected-(U10-6.OSC_OUT-Pad6)") (class "Default")
      (node (ref "U10") (pin "6") (pinfunction "6.OSC_OUT_6") (pintype "passive"))
    )
    (net (code "48") (name "unconnected-(U10-15.PA5-Pad15)") (class "Default")
      (node (ref "U10") (pin "15") (pinfunction "15.PA5_15") (pintype "passive"))
    )
    (net (code "49") (name "unconnected-(U10-16.PA6-Pad16)") (class "Default")
      (node (ref "U10") (pin "16") (pinfunction "16.PA6_16") (pintype "passive"))
    )
    (net (code "50") (name "unconnected-(U10-17.PA7-Pad17)") (class "Default")
      (node (ref "U10") (pin "17") (pinfunction "17.PA7_17") (pintype "passive"))
    )
    (net (code "51") (name "unconnected-(U10-20.PB2-Pad20)") (class "Default")
      (node (ref "U10") (pin "20") (pinfunction "20.PB2_20") (pintype "passive"))
    )
    (net (code "52") (name "unconnected-(U10-28.PB15-Pad28)") (class "Default")
      (node (ref "U10") (pin "28") (pinfunction "28.PB15_28") (pintype "passive"))
    )
    (net (code "53") (name "unconnected-(U10-33.PA12-Pad33)") (class "Default")
      (node (ref "U10") (pin "33") (pinfunction "33.PA12_33") (pintype "passive"))
    )
    (net (code "54") (name "unconnected-(U10-39.PB3-Pad39)") (class "Default")
      (node (ref "U10") (pin "39") (pinfunction "39.PB3_39") (pintype "passive"))
    )
    (net (code "55") (name "unconnected-(U10-40.PB4-Pad40)") (class "Default")
      (node (ref "U10") (pin "40") (pinfunction "40.PB4_40") (pintype "passive"))
    )
    (net (code "56") (name "unconnected-(U10-41.PB5-Pad41)") (class "Default")
      (node (ref "U10") (pin "41") (pinfunction "41.PB5_41") (pintype "passive"))
    )
    (net (code "57") (name "unconnected-(U10-42.PB6-Pad42)") (class "Default")
      (node (ref "U10") (pin "42") (pinfunction "42.PB6_42") (pintype "passive"))
    )
    (net (code "58") (name "unconnected-(U30-1.NC-Pad1)") (class "Default")
      (node (ref "U30") (pin "1") (pinfunction "1.NC_1") (pintype "passive"))
    )
    (net (code "59") (name "unconnected-(U30-3.P1_2-Pad3)") (class "Default")
      (node (ref "U30") (pin "3") (pinfunction "3.P1_2_3") (pintype "passive"))
    )
    (net (code "60") (name "unconnected-(U30-4.P1_3-Pad4)") (class "Default")
      (node (ref "U30") (pin "4") (pinfunction "4.P1_3_4") (pintype "passive"))
    )
    (net (code "61") (name "unconnected-(U30-5.P1_7-Pad5)") (class "Default")
      (node (ref "U30") (pin "5") (pinfunction "5.P1_7_5") (pintype "passive"))
    )
    (net (code "62") (name "unconnected-(U30-9.P3_6-Pad9)") (class "Default")
      (node (ref "U30") (pin "9") (pinfunction "9.P3_6_9") (pintype "passive"))
    )
    (net (code "63") (name "unconnected-(U30-11.P0_0-Pad11)") (class "Default")
      (node (ref "U30") (pin "11") (pinfunction "11.P0_0_11") (pintype "passive"))
    )
    (net (code "64") (name "unconnected-(U30-12.P0_2-Pad12)") (class "Default")
      (node (ref "U30") (pin "12") (pinfunction "12.P0_2_12") (pintype "passive"))
    )
    (net (code "65") (name "unconnected-(U30S-2.SIGN-Pad2)") (class "Default")
      (node (ref "U30S") (pin "2") (pinfunction "2.SIGN_2") (pintype "passive"))
    )
    (net (code "66") (name "~{BLE_RESET}") (class "Default")
      (node (ref "U10") (pin "19") (pinfunction "19.PB1_19") (pintype "passive"))
      (node (ref "U30") (pin "10") (pinfunction "10.~{RST}_10") (pintype "passive"))
    )
    (net (code "67") (name "~{BLE_RXI}") (class "Default")
      (node (ref "U10") (pin "25") (pinfunction "25.PB12_25") (pintype "passive"))
      (node (ref "U30") (pin "6") (pinfunction "6.P1_6_6") (pintype "passive"))
    )
    (net (code "68") (name "~{BLE_TXI}") (class "Default")
      (node (ref "U10") (pin "10") (pinfunction "10.PA0_10") (pintype "passive"))
      (node (ref "U30") (pin "15") (pinfunction "15.P2_7_15") (pintype "passive"))
    )
    (net (code "69") (name "~{RST}") (class "Default")
      (node (ref "C10R") (pin "1") (pinfunction "1_1") (pintype "passive"))
      (node (ref "SW10R") (pin "1") (pinfunction "1-2_1") (pintype "passive"))
      (node (ref "U10") (pin "7") (pinfunction "7.~{RST}_7") (pintype "passive"))
    )
    (net (code "70") (name "~{SENSOR_PWR}") (class "Default")
      (node (ref "R40P") (pin "2") (pinfunction "2_2") (pintype "passive"))
      (node (ref "T40P") (pin "1") (pinfunction "G_1") (pintype "bidirectional"))
      (node (ref "U10") (pin "46") (pinfunction "46.PB9_46") (pintype "passive"))
    )
  )
)
